# peripheral_uSD.net
KiCad netlist of a schematic drawn in Altium Designer
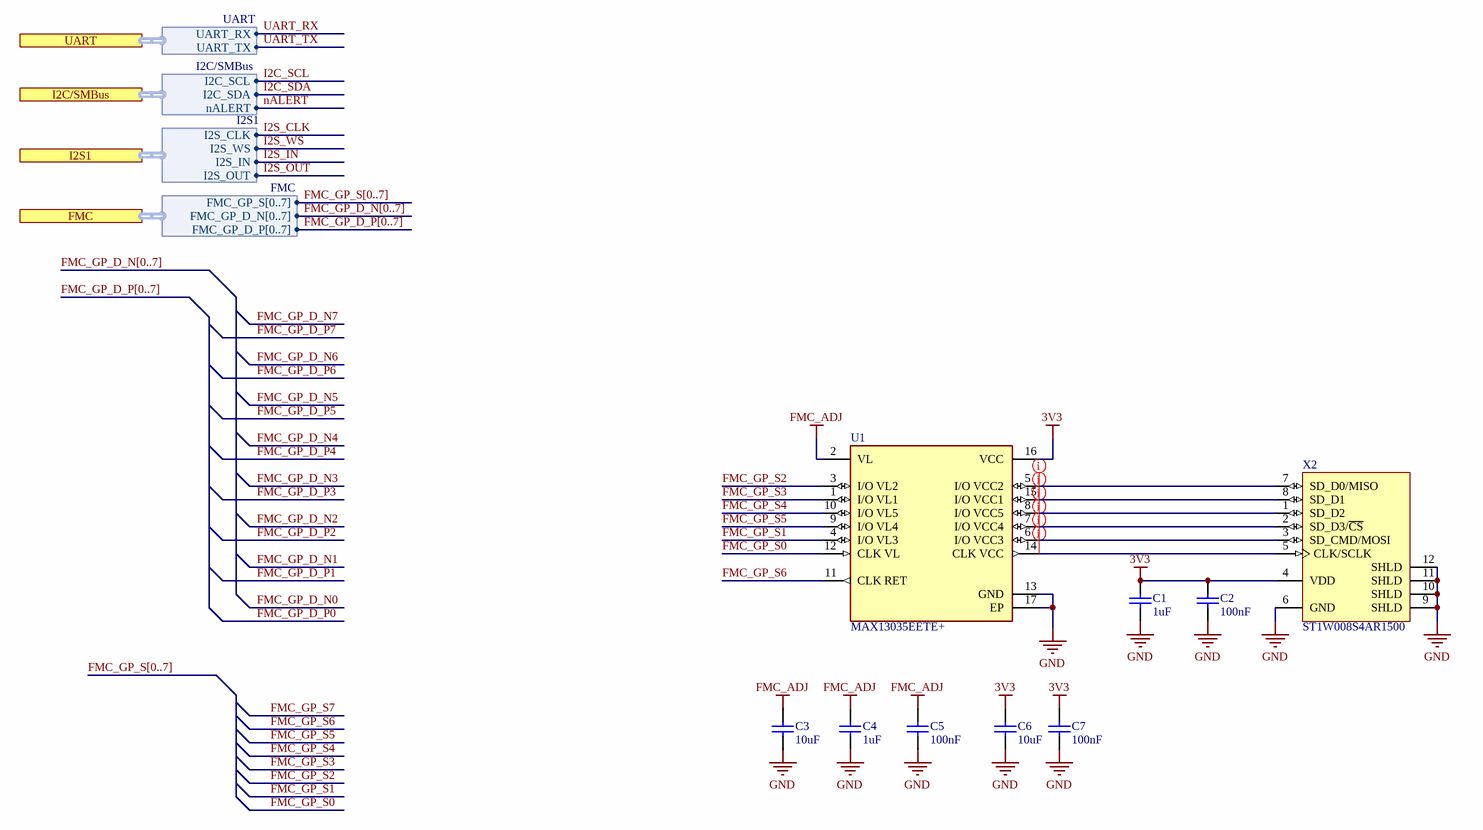
[diagram p0: peripheral_uSD.SchDoc]

(export (version "E")
  (design (tool "Eeschema 10.0.6"))
  (components
    (comp (ref "C1")
      (value "1uF")
      (footprint "CAPC1005X60X30LL05T10")
      (fields
        (field (name "PART NUMBER") "C0402C105K9PACTU")
        (field (name "MANUFACTURER") "Kemet")
        (field (name "TOLERANCE") "10%")
      )
      (libsource (lib "Altium Content Vault") (part "CAP"))
    )
    (comp (ref "C2")
      (value "100nF")
      (footprint "CAPC1050X55X23LL05T13")
      (description "Chip Capacitor, 100 nF, +/- 10%, 16 V, -55 to 125 degC, 0402 (1005 Metric), RoHS, Tape and Reel")
      (fields
        (field (name "MANUFACTURER") "Samsung Electro-Mechanics")
        (field (name "MANUFACTURER PART NUMBER") "CL05B104KO5NNNC")
      )
      (libsource (lib "Altium Content Vault") (part "CAP-NP-2"))
    )
    (comp (ref "C3")
      (value "10uF")
      (footprint "CAPC1608X90X35LL15T15")
      (fields
        (field (name "MANUFACTURER") "AVX Interconnect / Elco")
        (field (name "PART NUMBER") "06036D106MAT2A")
        (field (name "TOLERANCE") "20%")
      )
      (libsource (lib "Altium Content Vault") (part "CAP"))
    )
    (comp (ref "C4")
      (value "1uF")
      (footprint "CAPC1005X60X30LL05T10")
      (fields
        (field (name "PART NUMBER") "C0402C105K9PACTU")
        (field (name "MANUFACTURER") "Kemet")
        (field (name "TOLERANCE") "10%")
      )
      (libsource (lib "Altium Content Vault") (part "CAP"))
    )
    (comp (ref "C5")
      (value "100nF")
      (footprint "CAPC1050X55X23LL05T13")
      (description "Chip Capacitor, 100 nF, +/- 10%, 16 V, -55 to 125 degC, 0402 (1005 Metric), RoHS, Tape and Reel")
      (fields
        (field (name "MANUFACTURER") "Samsung Electro-Mechanics")
        (field (name "MANUFACTURER PART NUMBER") "CL05B104KO5NNNC")
      )
      (libsource (lib "Altium Content Vault") (part "CAP-NP-2"))
    )
    (comp (ref "C6")
      (value "10uF")
      (footprint "CAPC1608X90X35LL15T15")
      (fields
        (field (name "MANUFACTURER") "AVX Interconnect / Elco")
        (field (name "PART NUMBER") "06036D106MAT2A")
        (field (name "TOLERANCE") "20%")
      )
      (libsource (lib "Altium Content Vault") (part "CAP"))
    )
    (comp (ref "C7")
      (value "100nF")
      (footprint "CAPC1050X55X23LL05T13")
      (description "Chip Capacitor, 100 nF, +/- 10%, 16 V, -55 to 125 degC, 0402 (1005 Metric), RoHS, Tape and Reel")
      (fields
        (field (name "MANUFACTURER") "Samsung Electro-Mechanics")
        (field (name "MANUFACTURER PART NUMBER") "CL05B104KO5NNNC")
      )
      (libsource (lib "Altium Content Vault") (part "CAP-NP-2"))
    )
    (comp (ref "U1")
      (value "MAX13035EETE+")
      (footprint "FP-T1644-4-MFG")
      (description "IC TRNSLTR BIDIRECTIONAL 16TQFN")
      (fields
        (field (name "OCTOPART") "https://octopart.com/max13035eete%2B-maxim+integrated-39866737")
        (field (name "MANUFACTURER") "Maxim")
      )
      (libsource (lib "Altium Content Vault") (part "590dd740af4c8fb04a5e1529406daff"))
    )
    (comp (ref "X2")
      (value "ST1W008S4AR1500")
      (footprint "ST1W008S4AR1500")
      (description "Memory Card Connectors MICRO SD HINGE TYPE OPEN on cover")
      (fields (field (name "MANUFACTURER") "JAE Electronics"))
      (libsource (lib "ETHZ Vault") (part "MicroSDCard"))
    )
  )
  (nets
    (net (code "23") (name "/FMC_GP_S0") (class "Default")
      (node (ref "U1") (pin "12") (pinfunction "CLK_VL_12") (pintype "input"))
    )
    (net (code "24") (name "/FMC_GP_S1") (class "Default")
      (node (ref "U1") (pin "4") (pinfunction "I/O_VL3_4") (pintype "bidirectional"))
    )
    (net (code "25") (name "/FMC_GP_S2") (class "Default")
      (node (ref "U1") (pin "3") (pinfunction "I/O_VL2_3") (pintype "bidirectional"))
    )
    (net (code "26") (name "/FMC_GP_S3") (class "Default")
      (node (ref "U1") (pin "1") (pinfunction "I/O_VL1_1") (pintype "bidirectional"))
    )
    (net (code "27") (name "/FMC_GP_S4") (class "Default")
      (node (ref "U1") (pin "10") (pinfunction "I/O_VL5_10") (pintype "bidirectional"))
    )
    (net (code "28") (name "/FMC_GP_S5") (class "Default")
      (node (ref "U1") (pin "9") (pinfunction "I/O_VL4_9") (pintype "bidirectional"))
    )
    (net (code "29") (name "/FMC_GP_S6") (class "Default")
      (node (ref "U1") (pin "11") (pinfunction "CLK_RET_11") (pintype "output"))
    )
    (net (code "45") (name "3V3") (class "Default")
      (node (ref "C1") (pin "2") (pinfunction "2_2") (pintype "passive"))
      (node (ref "C2") (pin "2") (pinfunction "2_2") (pintype "passive"))
      (node (ref "C6") (pin "2") (pinfunction "2_2") (pintype "passive"))
      (node (ref "C7") (pin "2") (pinfunction "2_2") (pintype "passive"))
      (node (ref "U1") (pin "16") (pinfunction "VCC_16") (pintype "power_in"))
      (node (ref "X2") (pin "4") (pinfunction "VDD_4") (pintype "power_in"))
    )
    (net (code "46") (name "FMC_ADJ") (class "Default")
      (node (ref "C3") (pin "2") (pinfunction "2_2") (pintype "passive"))
      (node (ref "C4") (pin "2") (pinfunction "2_2") (pintype "passive"))
      (node (ref "C5") (pin "2") (pinfunction "2_2") (pintype "passive"))
      (node (ref "U1") (pin "2") (pinfunction "VL_2") (pintype "power_in"))
    )
    (net (code "47") (name "GND") (class "Default")
      (node (ref "C1") (pin "1") (pinfunction "1_1") (pintype "passive"))
      (node (ref "C2") (pin "1") (pinfunction "1_1") (pintype "passive"))
      (node (ref "C3") (pin "1") (pinfunction "1_1") (pintype "passive"))
      (node (ref "C4") (pin "1") (pinfunction "1_1") (pintype "passive"))
      (node (ref "C5") (pin "1") (pinfunction "1_1") (pintype "passive"))
      (node (ref "C6") (pin "1") (pinfunction "1_1") (pintype "passive"))
      (node (ref "C7") (pin "1") (pinfunction "1_1") (pintype "passive"))
      (node (ref "U1") (pin "13") (pinfunction "GND_13") (pintype "power_in"))
      (node (ref "U1") (pin "17") (pinfunction "EP_17") (pintype "power_in"))
      (node (ref "X2") (pin "10") (pinfunction "SHLD_10") (pintype "power_in"))
      (node (ref "X2") (pin "11") (pinfunction "SHLD_11") (pintype "power_in"))
      (node (ref "X2") (pin "12") (pinfunction "SHLD_12") (pintype "power_in"))
      (node (ref "X2") (pin "6") (pinfunction "GND_6") (pintype "power_in"))
      (node (ref "X2") (pin "9") (pinfunction "SHLD_9") (pintype "power_in"))
    )
    (net (code "48") (name "Net-(U1-CLK_VCC)") (class "Default")
      (node (ref "U1") (pin "14") (pinfunction "CLK_VCC_14") (pintype "output"))
      (node (ref "X2") (pin "5") (pinfunction "CLK/SCLK_5") (pintype "input"))
    )
    (net (code "49") (name "Net-(U1-I{slash}O_VCC1)") (class "Default")
      (node (ref "U1") (pin "15") (pinfunction "I/O_VCC1_15") (pintype "bidirectional"))
      (node (ref "X2") (pin "8") (pinfunction "SD_D1_8") (pintype "bidirectional"))
    )
    (net (code "50") (name "Net-(U1-I{slash}O_VCC2)") (class "Default")
      (node (ref "U1") (pin "5") (pinfunction "I/O_VCC2_5") (pintype "bidirectional"))
      (node (ref "X2") (pin "7") (pinfunction "SD_D0/MISO_7") (pintype "bidirectional"))
    )
    (net (code "51") (name "Net-(U1-I{slash}O_VCC3)") (class "Default")
      (node (ref "U1") (pin "6") (pinfunction "I/O_VCC3_6") (pintype "bidirectional"))
      (node (ref "X2") (pin "3") (pinfunction "SD_CMD/MOSI_3") (pintype "bidirectional"))
    )
    (net (code "52") (name "Net-(U1-I{slash}O_VCC4)") (class "Default")
      (node (ref "U1") (pin "7") (pinfunction "I/O_VCC4_7") (pintype "bidirectional"))
      (node (ref "X2") (pin "2") (pinfunction "SD_D3/~{CS}_2") (pintype "bidirectional"))
    )
    (net (code "53") (name "Net-(U1-I{slash}O_VCC5)") (class "Default")
      (node (ref "U1") (pin "8") (pinfunction "I/O_VCC5_8") (pintype "bidirectional"))
      (node (ref "X2") (pin "1") (pinfunction "SD_D2_1") (pintype "bidirectional"))
    )
  )
)
